# MCU.net
KiCad netlist of a schematic drawn in Altium Designer
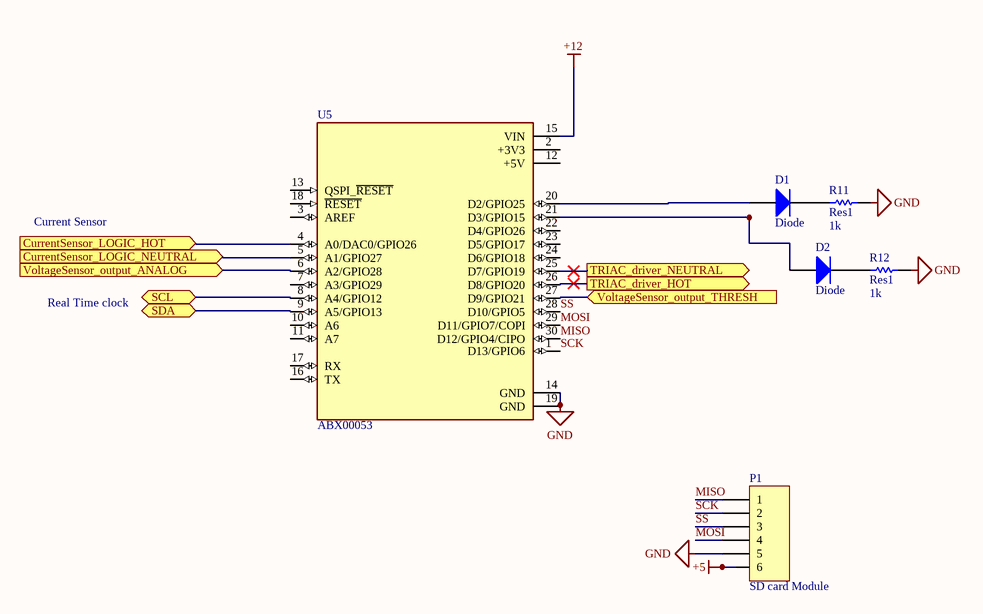
[diagram p0: MCU.SchDoc]

(export (version "E")
  (design (tool "Eeschema 10.0.6"))
  (components
    (comp (ref "D1")
      (value "Diode")
      (footprint "0603")
      (description "Default Diode")
      (fields (field (name "PUBLISHER") "Altium Limited"))
      (libsource (lib "Miscellaneous Devices") (part "Diode"))
    )
    (comp (ref "D2")
      (value "Diode")
      (footprint "0603")
      (description "Default Diode")
      (fields (field (name "PUBLISHER") "Altium Limited"))
      (libsource (lib "Miscellaneous Devices") (part "Diode"))
    )
    (comp (ref "P1")
      (value "SD card Module")
      (footprint "HDR1X6")
      (description "Header, 6-Pin")
      (fields (field (name "PUBLISHER") "Altium Limited"))
      (libsource (lib "Miscellaneous Connectors") (part "Header 6"))
    )
    (comp (ref "R11")
      (value "Res1")
      (footprint "0603")
      (description "Resistor")
      (fields (field (name "ALTIUM_VALUE") "1k") (field (name "PUBLISHER") "Altium Limited"))
      (libsource (lib "Miscellaneous Devices") (part "Res1"))
    )
    (comp (ref "R12")
      (value "Res1")
      (footprint "0603")
      (description "Resistor")
      (fields (field (name "ALTIUM_VALUE") "1k") (field (name "PUBLISHER") "Altium Limited"))
      (libsource (lib "Miscellaneous Devices") (part "Res1"))
    )
    (comp (ref "U5")
      (value "ABX00053")
      (footprint "MODULE_ABX00053")
      (fields (field (name "MF") "Arduino") (field (name "DIGI-KEY_PART_NUMBER") "1050-ABX00053-ND"))
      (libsource (lib "ABX00053") (part "ABX00053"))
    )
  )
  (nets
    (net (code "1") (name "+5") (class "Default")
      (node (ref "P1") (pin "6") (pinfunction "6_6") (pintype "passive"))
    )
    (net (code "2") (name "+12") (class "Default")
      (node (ref "U5") (pin "15") (pinfunction "VIN_15") (pintype "power_in"))
    )
    (net (code "4") (name "/CurrentSensor_LOGIC_HOT") (class "Default")
      (node (ref "U5") (pin "4") (pinfunction "A0/DAC0/GPIO26_4") (pintype "bidirectional"))
    )
    (net (code "5") (name "/CurrentSensor_LOGIC_NEUTRAL") (class "Default")
      (node (ref "U5") (pin "5") (pinfunction "A1/GPIO27_5") (pintype "bidirectional"))
    )
    (net (code "6") (name "/MISO") (class "Default")
      (node (ref "P1") (pin "1") (pinfunction "1_1") (pintype "passive"))
      (node (ref "U5") (pin "30") (pinfunction "D12/GPIO4/CIPO_30") (pintype "bidirectional"))
    )
    (net (code "7") (name "/MOSI") (class "Default")
      (node (ref "P1") (pin "4") (pinfunction "4_4") (pintype "passive"))
      (node (ref "U5") (pin "29") (pinfunction "D11/GPIO7/COPI_29") (pintype "bidirectional"))
    )
    (net (code "8") (name "/SCK") (class "Default")
      (node (ref "P1") (pin "2") (pinfunction "2_2") (pintype "passive"))
      (node (ref "U5") (pin "1") (pinfunction "D13/GPIO6_1") (pintype "bidirectional"))
    )
    (net (code "9") (name "/SCL") (class "Default")
      (node (ref "U5") (pin "8") (pinfunction "A4/GPIO12_8") (pintype "bidirectional"))
    )
    (net (code "10") (name "/SDA") (class "Default")
      (node (ref "U5") (pin "9") (pinfunction "A5/GPIO13_9") (pintype "bidirectional"))
    )
    (net (code "11") (name "/SS") (class "Default")
      (node (ref "P1") (pin "3") (pinfunction "3_3") (pintype "passive"))
      (node (ref "U5") (pin "28") (pinfunction "D10/GPIO5_28") (pintype "bidirectional"))
    )
    (net (code "12") (name "/TRIAC_driver_HOT") (class "Default")
      (node (ref "U5") (pin "26") (pinfunction "D8/GPIO20_26") (pintype "bidirectional"))
    )
    (net (code "13") (name "/TRIAC_driver_NEUTRAL") (class "Default")
      (node (ref "U5") (pin "25") (pinfunction "D7/GPIO19_25") (pintype "bidirectional"))
    )
    (net (code "14") (name "/VoltageSensor_output_ANALOG") (class "Default")
      (node (ref "U5") (pin "6") (pinfunction "A2/GPIO28_6") (pintype "bidirectional"))
    )
    (net (code "15") (name "/VoltageSensor_output_THRESH") (class "Default")
      (node (ref "U5") (pin "27") (pinfunction "D9/GPIO21_27") (pintype "bidirectional"))
    )
    (net (code "16") (name "GND") (class "Default")
      (node (ref "P1") (pin "5") (pinfunction "5_5") (pintype "passive"))
      (node (ref "R11") (pin "1") (pinfunction "1_1") (pintype "passive"))
      (node (ref "R12") (pin "1") (pinfunction "1_1") (pintype "passive"))
      (node (ref "U5") (pin "14") (pinfunction "GND_14") (pintype "power_in"))
      (node (ref "U5") (pin "19") (pinfunction "GND_19") (pintype "power_in"))
    )
    (net (code "17") (name "Net-(D1-A)") (class "Default")
      (node (ref "D1") (pin "1") (pinfunction "A_1") (pintype "passive"))
      (node (ref "U5") (pin "20") (pinfunction "D2/GPIO25_20") (pintype "bidirectional"))
    )
    (net (code "18") (name "Net-(D1-K)") (class "Default")
      (node (ref "D1") (pin "2") (pinfunction "K_2") (pintype "passive"))
      (node (ref "R11") (pin "2") (pinfunction "2_2") (pintype "passive"))
    )
    (net (code "19") (name "Net-(D2-A)") (class "Default")
      (node (ref "D2") (pin "1") (pinfunction "A_1") (pintype "passive"))
      (node (ref "U5") (pin "21") (pinfunction "D3/GPIO15_21") (pintype "bidirectional"))
    )
    (net (code "20") (name "Net-(D2-K)") (class "Default")
      (node (ref "D2") (pin "2") (pinfunction "K_2") (pintype "passive"))
      (node (ref "R12") (pin "2") (pinfunction "2_2") (pintype "passive"))
    )
    (net (code "21") (name "unconnected-(U5-+3V3-Pad2)") (class "Default")
      (node (ref "U5") (pin "2") (pinfunction "+3V3_2") (pintype "power_in"))
    )
    (net (code "22") (name "unconnected-(U5-+5V-Pad12)") (class "Default")
      (node (ref "U5") (pin "12") (pinfunction "+5V_12") (pintype "power_in"))
    )
    (net (code "23") (name "unconnected-(U5-A3{slash}GPIO29-Pad7)") (class "Default")
      (node (ref "U5") (pin "7") (pinfunction "A3/GPIO29_7") (pintype "bidirectional"))
    )
    (net (code "24") (name "unconnected-(U5-A6-Pad10)") (class "Default")
      (node (ref "U5") (pin "10") (pinfunction "A6_10") (pintype "bidirectional"))
    )
    (net (code "25") (name "unconnected-(U5-A7-Pad11)") (class "Default")
      (node (ref "U5") (pin "11") (pinfunction "A7_11") (pintype "bidirectional"))
    )
    (net (code "26") (name "unconnected-(U5-AREF-Pad3)") (class "Default")
      (node (ref "U5") (pin "3") (pinfunction "AREF_3") (pintype "bidirectional"))
    )
    (net (code "27") (name "unconnected-(U5-D4{slash}GPIO26-Pad22)") (class "Default")
      (node (ref "U5") (pin "22") (pinfunction "D4/GPIO26_22") (pintype "bidirectional"))
    )
    (net (code "28") (name "unconnected-(U5-D5{slash}GPIO17-Pad23)") (class "Default")
      (node (ref "U5") (pin "23") (pinfunction "D5/GPIO17_23") (pintype "bidirectional"))
    )
    (net (code "29") (name "unconnected-(U5-D6{slash}GPIO18-Pad24)") (class "Default")
      (node (ref "U5") (pin "24") (pinfunction "D6/GPIO18_24") (pintype "bidirectional"))
    )
    (net (code "30") (name "unconnected-(U5-QSPI_~{RESET}-Pad13)") (class "Default")
      (node (ref "U5") (pin "13") (pinfunction "QSPI_~{RESET}_13") (pintype "input"))
    )
    (net (code "31") (name "unconnected-(U5-RX-Pad17)") (class "Default")
      (node (ref "U5") (pin "17") (pinfunction "RX_17") (pintype "bidirectional"))
    )
    (net (code "32") (name "unconnected-(U5-TX-Pad16)") (class "Default")
      (node (ref "U5") (pin "16") (pinfunction "TX_16") (pintype "bidirectional"))
    )
    (net (code "33") (name "unconnected-(U5-~{RESET}-Pad18)") (class "Default")
      (node (ref "U5") (pin "18") (pinfunction "~{RESET}_18") (pintype "input"))
    )
  )
)
